# electricals_with_iPod.net
KiCad netlist of a schematic drawn in EAGLE
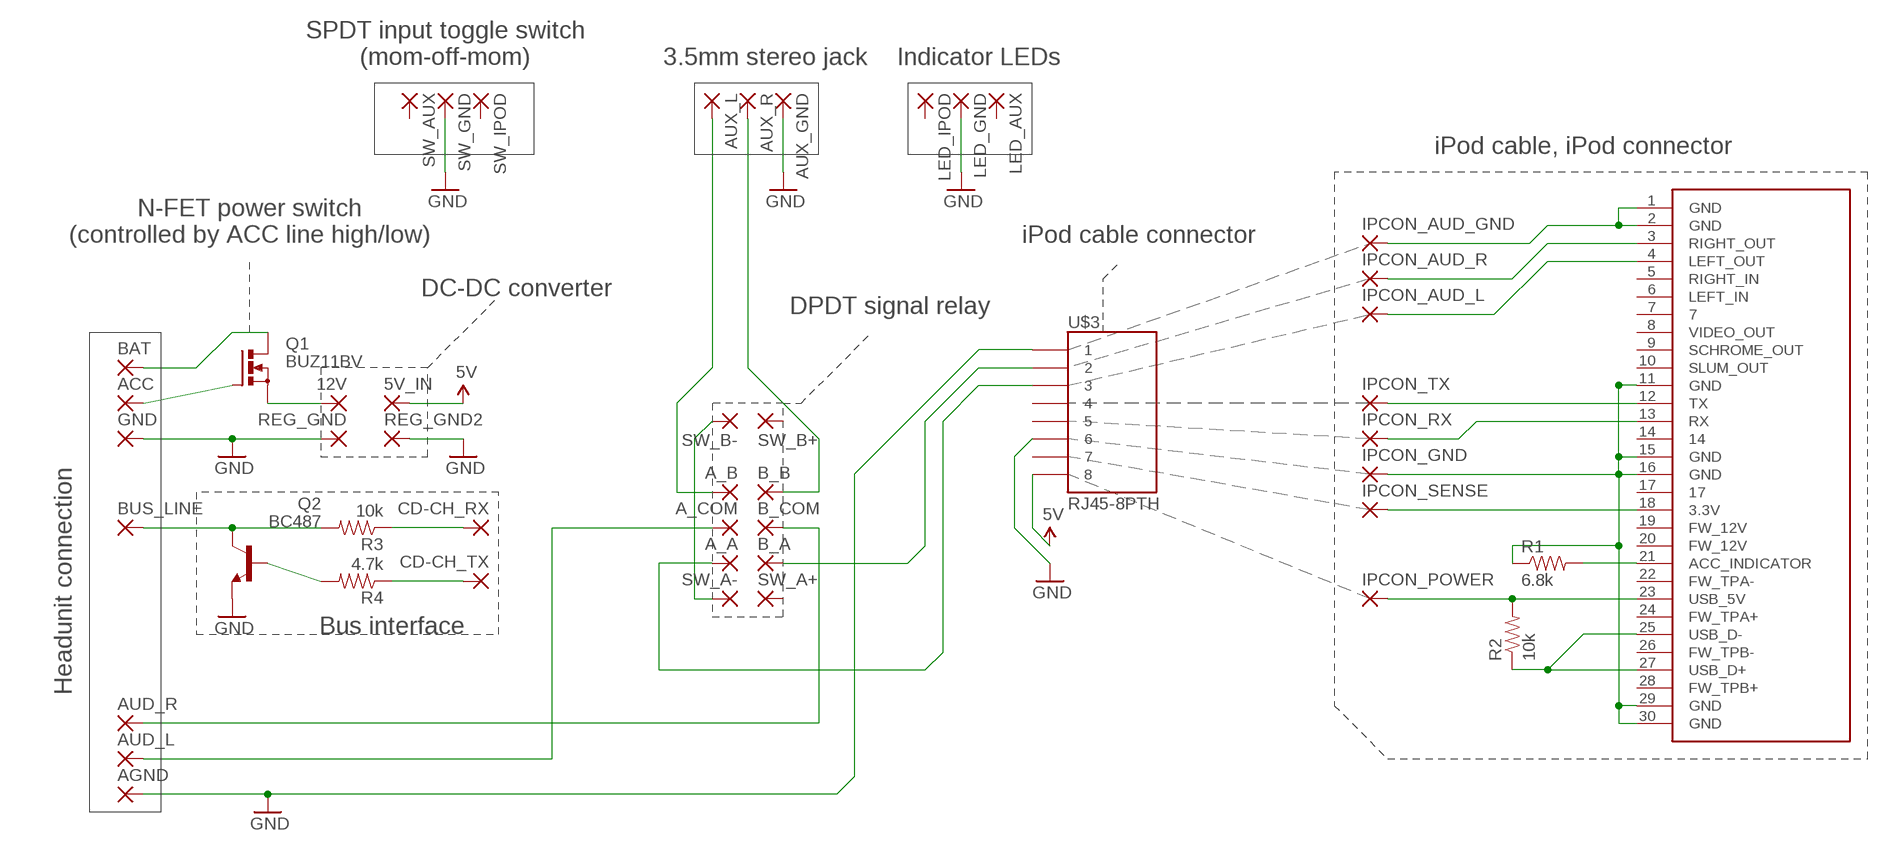
[diagram p0: schematic, sheet 1]

(export (version "E")
  (design (tool "Eeschema 10.0.6"))
  (components
    (comp (ref "5V_IN")
      (value "2,54/1,1")
      (footprint "eagle-import:2,54_1,1")
      (libsource (lib "eagle-import") (part "2,54/1,1"))
    )
    (comp (ref "12V")
      (value "2,54/1,1")
      (footprint "eagle-import:2,54_1,1")
      (libsource (lib "eagle-import") (part "2,54/1,1"))
    )
    (comp (ref "ACC")
      (value "1,6/0,9")
      (footprint "eagle-import:1,6_0,9")
      (libsource (lib "eagle-import") (part "1,6/0,9"))
    )
    (comp (ref "AGND")
      (value "1,6/0,9")
      (footprint "eagle-import:1,6_0,9")
      (libsource (lib "eagle-import") (part "1,6/0,9"))
    )
    (comp (ref "AUD_L")
      (value "1,6/0,9")
      (footprint "eagle-import:1,6_0,9")
      (libsource (lib "eagle-import") (part "1,6/0,9"))
    )
    (comp (ref "AUD_R")
      (value "1,6/0,9")
      (footprint "eagle-import:1,6_0,9")
      (libsource (lib "eagle-import") (part "1,6/0,9"))
    )
    (comp (ref "AUX_GND")
      (value "1,6/0,9")
      (footprint "eagle-import:1,6_0,9")
      (libsource (lib "eagle-import") (part "1,6/0,9"))
    )
    (comp (ref "AUX_L")
      (value "1,6/0,9")
      (footprint "eagle-import:1,6_0,9")
      (libsource (lib "eagle-import") (part "1,6/0,9"))
    )
    (comp (ref "AUX_R")
      (value "1,6/0,9")
      (footprint "eagle-import:1,6_0,9")
      (libsource (lib "eagle-import") (part "1,6/0,9"))
    )
    (comp (ref "A_A")
      (value "1,6/0,9")
      (footprint "eagle-import:1,6_0,9")
      (libsource (lib "eagle-import") (part "1,6/0,9"))
    )
    (comp (ref "A_B")
      (value "1,6/0,9")
      (footprint "eagle-import:1,6_0,9")
      (libsource (lib "eagle-import") (part "1,6/0,9"))
    )
    (comp (ref "A_COM")
      (value "1,6/0,9")
      (footprint "eagle-import:1,6_0,9")
      (libsource (lib "eagle-import") (part "1,6/0,9"))
    )
    (comp (ref "BAT")
      (value "2,54/1,1")
      (footprint "eagle-import:2,54_1,1")
      (libsource (lib "eagle-import") (part "2,54/1,1"))
    )
    (comp (ref "BUS_LINE")
      (value "1,6/0,9")
      (footprint "eagle-import:1,6_0,9")
      (libsource (lib "eagle-import") (part "1,6/0,9"))
    )
    (comp (ref "B_A")
      (value "1,6/0,9")
      (footprint "eagle-import:1,6_0,9")
      (libsource (lib "eagle-import") (part "1,6/0,9"))
    )
    (comp (ref "B_B")
      (value "1,6/0,9")
      (footprint "eagle-import:1,6_0,9")
      (libsource (lib "eagle-import") (part "1,6/0,9"))
    )
    (comp (ref "B_COM")
      (value "1,6/0,9")
      (footprint "eagle-import:1,6_0,9")
      (libsource (lib "eagle-import") (part "1,6/0,9"))
    )
    (comp (ref "CD-CH_RX")
      (value "1,6/0,9")
      (footprint "eagle-import:1,6_0,9")
      (libsource (lib "eagle-import") (part "1,6/0,9"))
    )
    (comp (ref "CD-CH_TX")
      (value "1,6/0,9")
      (footprint "eagle-import:1,6_0,9")
      (libsource (lib "eagle-import") (part "1,6/0,9"))
    )
    (comp (ref "GND")
      (value "2,54/1,1")
      (footprint "eagle-import:2,54_1,1")
      (libsource (lib "eagle-import") (part "2,54/1,1"))
    )
    (comp (ref "IPCON_AUD_GND")
      (value "1,6/0,9")
      (footprint "eagle-import:1,6_0,9")
      (libsource (lib "eagle-import") (part "1,6/0,9"))
    )
    (comp (ref "IPCON_AUD_L")
      (value "1,6/0,9")
      (footprint "eagle-import:1,6_0,9")
      (libsource (lib "eagle-import") (part "1,6/0,9"))
    )
    (comp (ref "IPCON_AUD_R")
      (value "1,6/0,9")
      (footprint "eagle-import:1,6_0,9")
      (libsource (lib "eagle-import") (part "1,6/0,9"))
    )
    (comp (ref "IPCON_GND")
      (value "1,6/0,9")
      (footprint "eagle-import:1,6_0,9")
      (libsource (lib "eagle-import") (part "1,6/0,9"))
    )
    (comp (ref "IPCON_POWER")
      (value "1,6/0,9")
      (footprint "eagle-import:1,6_0,9")
      (libsource (lib "eagle-import") (part "1,6/0,9"))
    )
    (comp (ref "IPCON_RX")
      (value "1,6/0,9")
      (footprint "eagle-import:1,6_0,9")
      (libsource (lib "eagle-import") (part "1,6/0,9"))
    )
    (comp (ref "IPCON_SENSE")
      (value "1,6/0,9")
      (footprint "eagle-import:1,6_0,9")
      (libsource (lib "eagle-import") (part "1,6/0,9"))
    )
    (comp (ref "IPCON_TX")
      (value "1,6/0,9")
      (footprint "eagle-import:1,6_0,9")
      (libsource (lib "eagle-import") (part "1,6/0,9"))
    )
    (comp (ref "LED_AUX")
      (value "1,6/0,9")
      (footprint "eagle-import:1,6_0,9")
      (libsource (lib "eagle-import") (part "1,6/0,9"))
    )
    (comp (ref "LED_GND")
      (value "1,6/0,9")
      (footprint "eagle-import:1,6_0,9")
      (libsource (lib "eagle-import") (part "1,6/0,9"))
    )
    (comp (ref "LED_IPOD")
      (value "1,6/0,9")
      (footprint "eagle-import:1,6_0,9")
      (libsource (lib "eagle-import") (part "1,6/0,9"))
    )
    (comp (ref "Q1")
      (value "BUZ11BV")
      (footprint "eagle-import:TO220BV")
      (libsource (lib "eagle-import") (part "BUZ11BV"))
    )
    (comp (ref "Q2")
      (value "BC487")
      (footprint "eagle-import:TO92-EBC")
      (libsource (lib "eagle-import") (part "BC487"))
    )
    (comp (ref "R1")
      (value "6.8k")
      (footprint "eagle-import:1206")
      (libsource (lib "eagle-import") (part "RESISTOR1206"))
    )
    (comp (ref "R2")
      (value "10k")
      (footprint "eagle-import:1206")
      (libsource (lib "eagle-import") (part "RESISTOR1206"))
    )
    (comp (ref "R3")
      (value "10k")
      (footprint "eagle-import:1206")
      (libsource (lib "eagle-import") (part "RESISTOR1206"))
    )
    (comp (ref "R4")
      (value "4.7k")
      (footprint "eagle-import:1206")
      (libsource (lib "eagle-import") (part "RESISTOR1206"))
    )
    (comp (ref "REG_GND")
      (value "2,54/1,1")
      (footprint "eagle-import:2,54_1,1")
      (libsource (lib "eagle-import") (part "2,54/1,1"))
    )
    (comp (ref "REG_GND2")
      (value "2,54/1,1")
      (footprint "eagle-import:2,54_1,1")
      (libsource (lib "eagle-import") (part "2,54/1,1"))
    )
    (comp (ref "SW_A+")
      (value "1,6/0,9")
      (footprint "eagle-import:1,6_0,9")
      (libsource (lib "eagle-import") (part "1,6/0,9"))
    )
    (comp (ref "SW_A-")
      (value "1,6/0,9")
      (footprint "eagle-import:1,6_0,9")
      (libsource (lib "eagle-import") (part "1,6/0,9"))
    )
    (comp (ref "SW_AUX")
      (value "1,6/0,9")
      (footprint "eagle-import:1,6_0,9")
      (libsource (lib "eagle-import") (part "1,6/0,9"))
    )
    (comp (ref "SW_B+")
      (value "1,6/0,9")
      (footprint "eagle-import:1,6_0,9")
      (libsource (lib "eagle-import") (part "1,6/0,9"))
    )
    (comp (ref "SW_B-")
      (value "1,6/0,9")
      (footprint "eagle-import:1,6_0,9")
      (libsource (lib "eagle-import") (part "1,6/0,9"))
    )
    (comp (ref "SW_GND")
      (value "1,6/0,9")
      (footprint "eagle-import:1,6_0,9")
      (libsource (lib "eagle-import") (part "1,6/0,9"))
    )
    (comp (ref "SW_IPOD")
      (value "1,6/0,9")
      (footprint "eagle-import:1,6_0,9")
      (libsource (lib "eagle-import") (part "1,6/0,9"))
    )
    (comp (ref "U$1")
      (value "IPOD_CONNECTOR_MALE")
      (footprint "eagle-import:IPOD_MALE_CONNECTOR")
      (libsource (lib "eagle-import") (part "IPOD_CONNECTOR_MALE"))
    )
    (comp (ref "U$3")
      (value "RJ45-8PTH")
      (footprint "eagle-import:RJ45-8")
      (libsource (lib "eagle-import") (part "RJ45-8PTH"))
    )
  )
  (nets
    (net (code "1") (name "5V") (class "Default")
      (node (ref "5V_IN") (pin "1") (pinfunction "P_1") (pintype "passive"))
      (node (ref "U$3") (pin "8") (pinfunction "8_8") (pintype "bidirectional"))
    )
    (net (code "2") (name "GND") (class "Default")
      (node (ref "AGND") (pin "1") (pinfunction "P_1") (pintype "passive"))
      (node (ref "AUX_GND") (pin "1") (pinfunction "P_1") (pintype "passive"))
      (node (ref "GND") (pin "1") (pinfunction "P_1") (pintype "passive"))
      (node (ref "LED_GND") (pin "1") (pinfunction "P_1") (pintype "passive"))
      (node (ref "Q2") (pin "E") (pinfunction "E_E") (pintype "passive"))
      (node (ref "REG_GND") (pin "1") (pinfunction "P_1") (pintype "passive"))
      (node (ref "REG_GND2") (pin "1") (pinfunction "P_1") (pintype "passive"))
      (node (ref "SW_GND") (pin "1") (pinfunction "P_1") (pintype "passive"))
      (node (ref "U$3") (pin "1") (pinfunction "1_1") (pintype "bidirectional"))
      (node (ref "U$3") (pin "6") (pinfunction "6_6") (pintype "bidirectional"))
    )
    (net (code "3") (name "Net-(12V-P)") (class "Default")
      (node (ref "12V") (pin "1") (pinfunction "P_1") (pintype "passive"))
      (node (ref "Q1") (pin "S") (pinfunction "S_S") (pintype "passive"))
    )
    (net (code "4") (name "Net-(ACC-P)") (class "Default")
      (node (ref "ACC") (pin "1") (pinfunction "P_1") (pintype "passive"))
      (node (ref "Q1") (pin "G") (pinfunction "G_G") (pintype "passive"))
    )
    (net (code "5") (name "Net-(AUD_L-P)") (class "Default")
      (node (ref "AUD_L") (pin "1") (pinfunction "P_1") (pintype "passive"))
      (node (ref "A_COM") (pin "1") (pinfunction "P_1") (pintype "passive"))
    )
    (net (code "6") (name "Net-(AUD_R-P)") (class "Default")
      (node (ref "AUD_R") (pin "1") (pinfunction "P_1") (pintype "passive"))
      (node (ref "B_COM") (pin "1") (pinfunction "P_1") (pintype "passive"))
    )
    (net (code "7") (name "Net-(AUX_L-P)") (class "Default")
      (node (ref "AUX_L") (pin "1") (pinfunction "P_1") (pintype "passive"))
      (node (ref "A_B") (pin "1") (pinfunction "P_1") (pintype "passive"))
    )
    (net (code "8") (name "Net-(AUX_R-P)") (class "Default")
      (node (ref "AUX_R") (pin "1") (pinfunction "P_1") (pintype "passive"))
      (node (ref "B_B") (pin "1") (pinfunction "P_1") (pintype "passive"))
    )
    (net (code "9") (name "Net-(A_A-P)") (class "Default")
      (node (ref "A_A") (pin "1") (pinfunction "P_1") (pintype "passive"))
      (node (ref "U$3") (pin "3") (pinfunction "3_3") (pintype "bidirectional"))
    )
    (net (code "10") (name "Net-(BAT-P)") (class "Default")
      (node (ref "BAT") (pin "1") (pinfunction "P_1") (pintype "passive"))
      (node (ref "Q1") (pin "D") (pinfunction "D_D") (pintype "passive"))
    )
    (net (code "11") (name "Net-(BUS_LINE-P)") (class "Default")
      (node (ref "BUS_LINE") (pin "1") (pinfunction "P_1") (pintype "passive"))
      (node (ref "Q2") (pin "C") (pinfunction "C_C") (pintype "passive"))
      (node (ref "R3") (pin "2") (pinfunction "2_2") (pintype "passive"))
    )
    (net (code "12") (name "Net-(B_A-P)") (class "Default")
      (node (ref "B_A") (pin "1") (pinfunction "P_1") (pintype "passive"))
      (node (ref "U$3") (pin "2") (pinfunction "2_2") (pintype "bidirectional"))
    )
    (net (code "13") (name "Net-(CD-CH_RX-P)") (class "Default")
      (node (ref "CD-CH_RX") (pin "1") (pinfunction "P_1") (pintype "passive"))
      (node (ref "R3") (pin "1") (pinfunction "1_1") (pintype "passive"))
    )
    (net (code "14") (name "Net-(CD-CH_TX-P)") (class "Default")
      (node (ref "CD-CH_TX") (pin "1") (pinfunction "P_1") (pintype "passive"))
      (node (ref "R4") (pin "1") (pinfunction "1_1") (pintype "passive"))
    )
    (net (code "15") (name "Net-(IPCON_AUD_GND-P)") (class "Default")
      (node (ref "IPCON_AUD_GND") (pin "1") (pinfunction "P_1") (pintype "passive"))
      (node (ref "U$1") (pin "1") (pinfunction "GND_1") (pintype "bidirectional"))
      (node (ref "U$1") (pin "2") (pinfunction "GND_2") (pintype "bidirectional"))
    )
    (net (code "16") (name "Net-(IPCON_AUD_L-P)") (class "Default")
      (node (ref "IPCON_AUD_L") (pin "1") (pinfunction "P_1") (pintype "passive"))
      (node (ref "U$1") (pin "4") (pinfunction "LEFT_OUT_4") (pintype "bidirectional"))
    )
    (net (code "17") (name "Net-(IPCON_AUD_R-P)") (class "Default")
      (node (ref "IPCON_AUD_R") (pin "1") (pinfunction "P_1") (pintype "passive"))
      (node (ref "U$1") (pin "3") (pinfunction "RIGHT_OUT_3") (pintype "bidirectional"))
    )
    (net (code "18") (name "Net-(IPCON_GND-P)") (class "Default")
      (node (ref "IPCON_GND") (pin "1") (pinfunction "P_1") (pintype "passive"))
      (node (ref "R1") (pin "1") (pinfunction "1_1") (pintype "passive"))
      (node (ref "U$1") (pin "11") (pinfunction "GND_11") (pintype "bidirectional"))
      (node (ref "U$1") (pin "15") (pinfunction "GND_15") (pintype "bidirectional"))
      (node (ref "U$1") (pin "16") (pinfunction "GND_16") (pintype "bidirectional"))
      (node (ref "U$1") (pin "29") (pinfunction "GND_29") (pintype "bidirectional"))
      (node (ref "U$1") (pin "30") (pinfunction "GND_30") (pintype "bidirectional"))
    )
    (net (code "19") (name "Net-(IPCON_POWER-P)") (class "Default")
      (node (ref "IPCON_POWER") (pin "1") (pinfunction "P_1") (pintype "passive"))
      (node (ref "R2") (pin "2") (pinfunction "2_2") (pintype "passive"))
      (node (ref "U$1") (pin "23") (pinfunction "USB_5V_23") (pintype "bidirectional"))
    )
    (net (code "20") (name "Net-(IPCON_RX-P)") (class "Default")
      (node (ref "IPCON_RX") (pin "1") (pinfunction "P_1") (pintype "passive"))
      (node (ref "U$1") (pin "13") (pinfunction "RX_13") (pintype "bidirectional"))
    )
    (net (code "21") (name "Net-(IPCON_SENSE-P)") (class "Default")
      (node (ref "IPCON_SENSE") (pin "1") (pinfunction "P_1") (pintype "passive"))
      (node (ref "U$1") (pin "18") (pinfunction "3.3V_18") (pintype "bidirectional"))
    )
    (net (code "22") (name "Net-(IPCON_TX-P)") (class "Default")
      (node (ref "IPCON_TX") (pin "1") (pinfunction "P_1") (pintype "passive"))
      (node (ref "U$1") (pin "12") (pinfunction "TX_12") (pintype "bidirectional"))
    )
    (net (code "23") (name "Net-(Q2-PadB)") (class "Default")
      (node (ref "Q2") (pin "B") (pinfunction "B_B") (pintype "passive"))
      (node (ref "R4") (pin "2") (pinfunction "2_2") (pintype "passive"))
    )
    (net (code "24") (name "Net-(SW_A--P)") (class "Default")
      (node (ref "SW_A-") (pin "1") (pinfunction "P_1") (pintype "passive"))
      (node (ref "SW_B-") (pin "1") (pinfunction "P_1") (pintype "passive"))
    )
    (net (code "25") (name "Net-(U$1-ACC_INDICATOR)") (class "Default")
      (node (ref "R1") (pin "2") (pinfunction "2_2") (pintype "passive"))
      (node (ref "U$1") (pin "21") (pinfunction "ACC_INDICATOR_21") (pintype "bidirectional"))
    )
    (net (code "26") (name "Net-(U$1-USB_D+)") (class "Default")
      (node (ref "R2") (pin "1") (pinfunction "1_1") (pintype "passive"))
      (node (ref "U$1") (pin "25") (pinfunction "USB_D-_25") (pintype "bidirectional"))
      (node (ref "U$1") (pin "27") (pinfunction "USB_D+_27") (pintype "bidirectional"))
    )
    (net (code "27") (name "unconnected-(LED_AUX-P-Pad1)") (class "Default")
      (node (ref "LED_AUX") (pin "1") (pinfunction "P_1") (pintype "passive"))
    )
    (net (code "28") (name "unconnected-(LED_IPOD-P-Pad1)") (class "Default")
      (node (ref "LED_IPOD") (pin "1") (pinfunction "P_1") (pintype "passive"))
    )
    (net (code "29") (name "unconnected-(SW_A+-P-Pad1)") (class "Default")
      (node (ref "SW_A+") (pin "1") (pinfunction "P_1") (pintype "passive"))
    )
    (net (code "30") (name "unconnected-(SW_AUX-P-Pad1)") (class "Default")
      (node (ref "SW_AUX") (pin "1") (pinfunction "P_1") (pintype "passive"))
    )
    (net (code "31") (name "unconnected-(SW_B+-P-Pad1)") (class "Default")
      (node (ref "SW_B+") (pin "1") (pinfunction "P_1") (pintype "passive"))
    )
    (net (code "32") (name "unconnected-(SW_IPOD-P-Pad1)") (class "Default")
      (node (ref "SW_IPOD") (pin "1") (pinfunction "P_1") (pintype "passive"))
    )
    (net (code "33") (name "unconnected-(U$1-FW_12V-Pad19)") (class "Default")
      (node (ref "U$1") (pin "19") (pinfunction "FW_12V_19") (pintype "bidirectional"))
    )
    (net (code "34") (name "unconnected-(U$1-FW_12V-Pad20)") (class "Default")
      (node (ref "U$1") (pin "20") (pinfunction "FW_12V_20") (pintype "bidirectional"))
    )
    (net (code "35") (name "unconnected-(U$1-FW_TPA+-Pad24)") (class "Default")
      (node (ref "U$1") (pin "24") (pinfunction "FW_TPA+_24") (pintype "bidirectional"))
    )
    (net (code "36") (name "unconnected-(U$1-FW_TPA--Pad22)") (class "Default")
      (node (ref "U$1") (pin "22") (pinfunction "FW_TPA-_22") (pintype "bidirectional"))
    )
    (net (code "37") (name "unconnected-(U$1-FW_TPB+-Pad28)") (class "Default")
      (node (ref "U$1") (pin "28") (pinfunction "FW_TPB+_28") (pintype "bidirectional"))
    )
    (net (code "38") (name "unconnected-(U$1-FW_TPB--Pad26)") (class "Default")
      (node (ref "U$1") (pin "26") (pinfunction "FW_TPB-_26") (pintype "bidirectional"))
    )
    (net (code "39") (name "unconnected-(U$1-LEFT_IN-Pad6)") (class "Default")
      (node (ref "U$1") (pin "6") (pinfunction "LEFT_IN_6") (pintype "bidirectional"))
    )
    (net (code "40") (name "unconnected-(U$1-Pad7)") (class "Default")
      (node (ref "U$1") (pin "7") (pinfunction "7_7") (pintype "bidirectional"))
    )
    (net (code "41") (name "unconnected-(U$1-Pad14)") (class "Default")
      (node (ref "U$1") (pin "14") (pinfunction "14_14") (pintype "bidirectional"))
    )
    (net (code "42") (name "unconnected-(U$1-Pad17)") (class "Default")
      (node (ref "U$1") (pin "17") (pinfunction "17_17") (pintype "bidirectional"))
    )
    (net (code "43") (name "unconnected-(U$1-RIGHT_IN-Pad5)") (class "Default")
      (node (ref "U$1") (pin "5") (pinfunction "RIGHT_IN_5") (pintype "bidirectional"))
    )
    (net (code "44") (name "unconnected-(U$1-SCHROME_OUT-Pad9)") (class "Default")
      (node (ref "U$1") (pin "9") (pinfunction "SCHROME_OUT_9") (pintype "bidirectional"))
    )
    (net (code "45") (name "unconnected-(U$1-SLUM_OUT-Pad10)") (class "Default")
      (node (ref "U$1") (pin "10") (pinfunction "SLUM_OUT_10") (pintype "bidirectional"))
    )
    (net (code "46") (name "unconnected-(U$1-VIDEO_OUT-Pad8)") (class "Default")
      (node (ref "U$1") (pin "8") (pinfunction "VIDEO_OUT_8") (pintype "bidirectional"))
    )
    (net (code "47") (name "unconnected-(U$3-Pad4)") (class "Default")
      (node (ref "U$3") (pin "4") (pinfunction "4_4") (pintype "bidirectional"))
    )
    (net (code "48") (name "unconnected-(U$3-Pad5)") (class "Default")
      (node (ref "U$3") (pin "5") (pinfunction "5_5") (pintype "bidirectional"))
    )
    (net (code "49") (name "unconnected-(U$3-Pad7)") (class "Default")
      (node (ref "U$3") (pin "7") (pinfunction "7_7") (pintype "bidirectional"))
    )
  )
)
